# TCRT5000-Driver.net
KiCad netlist of a schematic drawn in EasyEDA
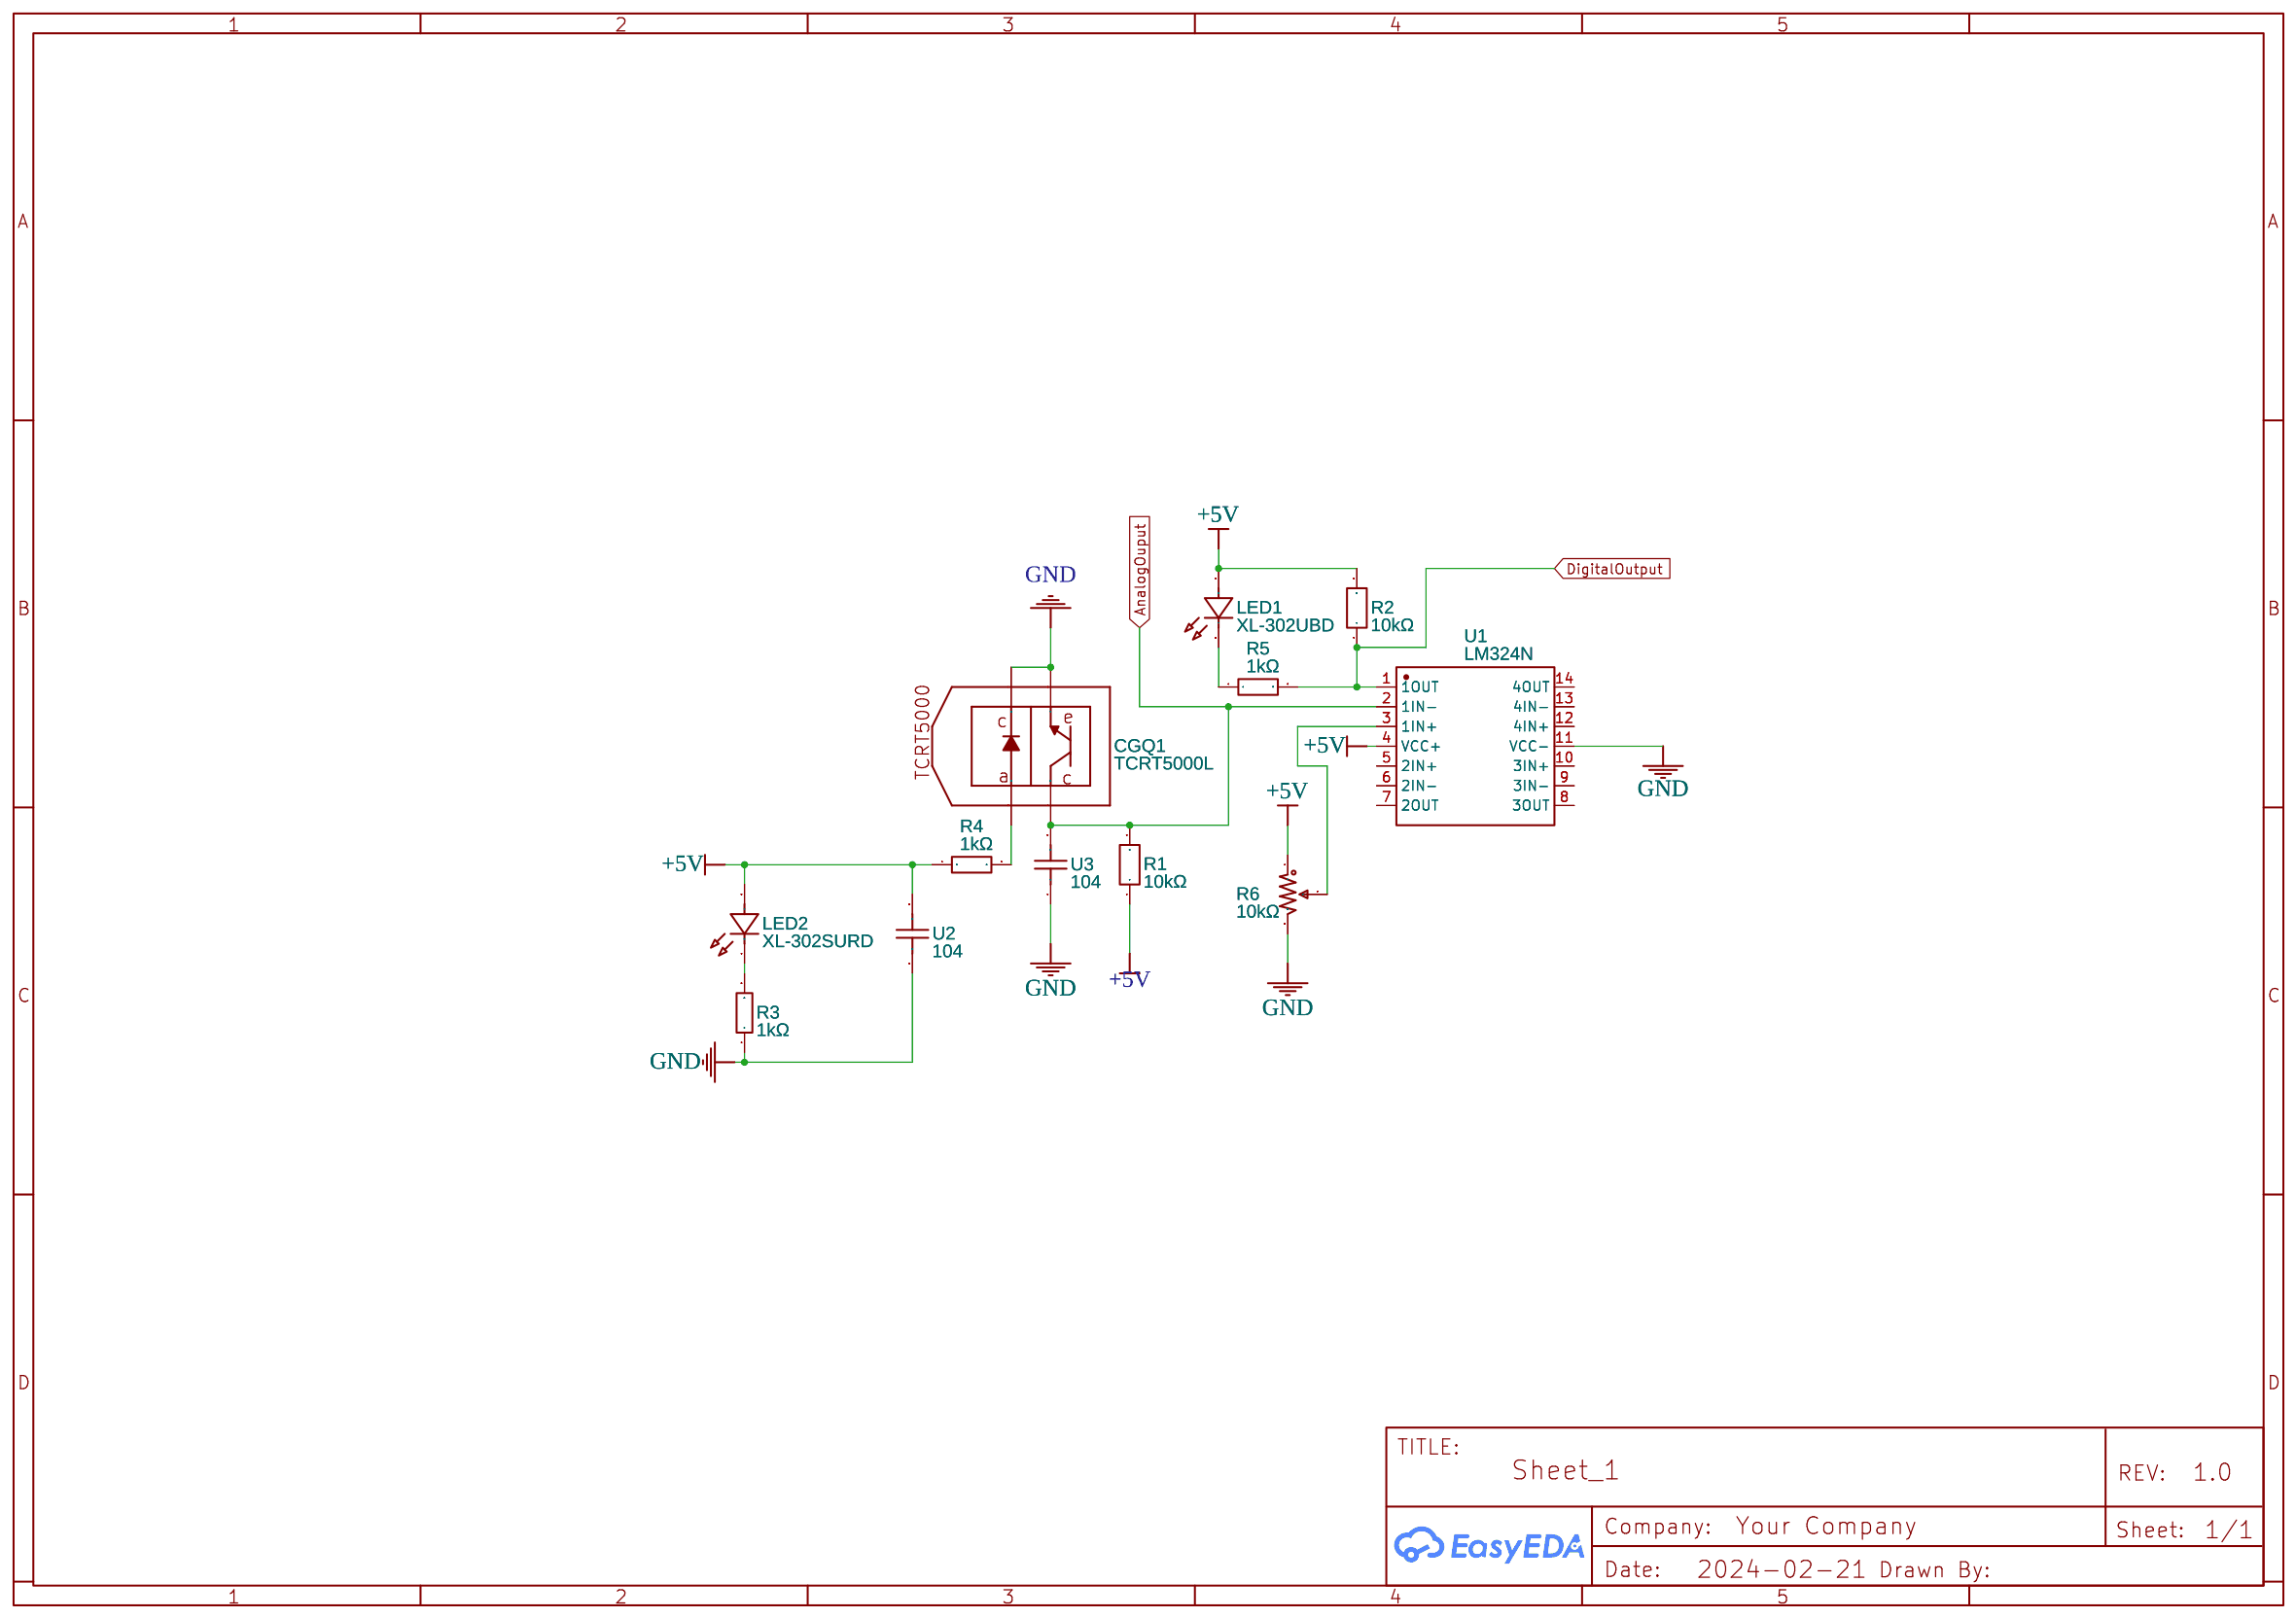
[diagram p0: schematic sheet]

(export (version "E")
  (design (tool "Eeschema 10.0.6"))
  (components
    (comp (ref "CGQ1")
      (value "TCRT5000L")
      (fields (field (name "Manufacturer") "VISHAY(威世)"))
      (libsource (lib "") (part "TCRT5000L"))
    )
    (comp (ref "LED1")
      (value "XL-302UBD")
      (fields (field (name "Manufacturer") "XINGLIGHT(成兴光)"))
      (libsource (lib "") (part "XL-302UBD"))
    )
    (comp (ref "LED2")
      (value "XL-302SURD")
      (fields (field (name "Manufacturer") "XINGLIGHT(成兴光)"))
      (libsource (lib "") (part "XL-302SURD"))
    )
    (comp (ref "R1")
      (value "10kΩ")
      (fields
        (field (name "Manufacturer Part") "RD1/4W10KJT/BA1")
        (field (name "Manufacturer") "Tyohm(幸亚电阻)")
      )
      (libsource (lib "") (part "RD 1/4W 10K J T/B A1"))
    )
    (comp (ref "R2")
      (value "10kΩ")
      (fields
        (field (name "Manufacturer Part") "RD1/4W10KJT/BA1")
        (field (name "Manufacturer") "Tyohm(幸亚电阻)")
      )
      (libsource (lib "") (part "RD 1/4W 10K J T/B A1"))
    )
    (comp (ref "R3")
      (value "1kΩ")
      (fields (field (name "Manufacturer Part") "CR1/4W-1K±5%-ST26") (field (name "Manufacturer") "VO(翔胜)"))
      (libsource (lib "") (part "CR1/4W-1K±5%-ST26_1"))
    )
    (comp (ref "R4")
      (value "1kΩ")
      (fields (field (name "Manufacturer Part") "CR1/4W-1K±5%-ST26") (field (name "Manufacturer") "VO(翔胜)"))
      (libsource (lib "") (part "CR1/4W-1K±5%-ST26"))
    )
    (comp (ref "R5")
      (value "1kΩ")
      (fields (field (name "Manufacturer Part") "CR1/4W-1K±5%-ST26") (field (name "Manufacturer") "VO(翔胜)"))
      (libsource (lib "") (part "CR1/4W-1K±5%-ST26"))
    )
    (comp (ref "R6")
      (value "10kΩ")
      (fields (field (name "Manufacturer Part") "RM065-103(10K)") (field (name "Manufacturer") "BOCHEN(博晨)"))
      (libsource (lib "") (part "RM065-103(10K)"))
    )
    (comp (ref "U1")
      (value "LM324N")
      (fields (field (name "Manufacturer") "TI(德州仪器)"))
      (libsource (lib "") (part "LM324N"))
    )
    (comp (ref "U2")
      (value "104")
      (fields
        (field (name "Manufacturer Part") "CC1H104MC1FD3F6C10SA")
        (field (name "Manufacturer") "Dersonic(德尔创)")
      )
      (libsource (lib "") (part "CC1H104MC1FD3F6C10SA"))
    )
    (comp (ref "U3")
      (value "104")
      (fields
        (field (name "Manufacturer Part") "CC1H104MC1FD3F6C10SA")
        (field (name "Manufacturer") "Dersonic(德尔创)")
      )
      (libsource (lib "") (part "CC1H104MC1FD3F6C10SA"))
    )
  )
  (nets
    (net (code "1") (name "+5V") (class "Default")
      (node (ref "LED1") (pin "1") (pinfunction "K_1") (pintype "unspecified"))
      (node (ref "LED2") (pin "2") (pinfunction "A_2") (pintype "unspecified"))
      (node (ref "R1") (pin "1") (pinfunction "1_1") (pintype "unspecified"))
      (node (ref "R2") (pin "2") (pinfunction "2_2") (pintype "unspecified"))
      (node (ref "R4") (pin "1") (pinfunction "1_1") (pintype "unspecified"))
      (node (ref "R6") (pin "1") (pinfunction "1_1") (pintype "unspecified"))
      (node (ref "U1") (pin "4") (pinfunction "VCC+_4") (pintype "unspecified"))
      (node (ref "U2") (pin "2") (pinfunction "2_2") (pintype "unspecified"))
    )
    (net (code "2") (name "AnalogOuput") (class "Default")
      (node (ref "CGQ1") (pin "1") (pinfunction "C_1") (pintype "unspecified"))
      (node (ref "R1") (pin "2") (pinfunction "2_2") (pintype "unspecified"))
      (node (ref "U1") (pin "2") (pinfunction "1IN-_2") (pintype "unspecified"))
      (node (ref "U3") (pin "2") (pinfunction "2_2") (pintype "unspecified"))
    )
    (net (code "3") (name "DigitalOutput") (class "Default")
      (node (ref "R2") (pin "1") (pinfunction "1_1") (pintype "unspecified"))
      (node (ref "R5") (pin "2") (pinfunction "2_2") (pintype "unspecified"))
      (node (ref "U1") (pin "1") (pinfunction "1OUT_1") (pintype "unspecified"))
    )
    (net (code "4") (name "GND") (class "Default")
      (node (ref "CGQ1") (pin "2") (pinfunction "E_2") (pintype "unspecified"))
      (node (ref "CGQ1") (pin "4") (pinfunction "C_4") (pintype "unspecified"))
      (node (ref "R3") (pin "1") (pinfunction "1_1") (pintype "unspecified"))
      (node (ref "R6") (pin "3") (pinfunction "3_3") (pintype "unspecified"))
      (node (ref "U1") (pin "11") (pinfunction "VCC-_11") (pintype "unspecified"))
      (node (ref "U2") (pin "1") (pinfunction "1_1") (pintype "unspecified"))
      (node (ref "U3") (pin "1") (pinfunction "1_1") (pintype "unspecified"))
    )
    (net (code "5") (name "Net-(CGQ1-A)") (class "Default")
      (node (ref "CGQ1") (pin "3") (pinfunction "A_3") (pintype "unspecified"))
      (node (ref "R4") (pin "2") (pinfunction "2_2") (pintype "unspecified"))
    )
    (net (code "6") (name "Net-(LED1-A)") (class "Default")
      (node (ref "LED1") (pin "2") (pinfunction "A_2") (pintype "unspecified"))
      (node (ref "R5") (pin "1") (pinfunction "1_1") (pintype "unspecified"))
    )
    (net (code "7") (name "Net-(LED2-K)") (class "Default")
      (node (ref "LED2") (pin "1") (pinfunction "K_1") (pintype "unspecified"))
      (node (ref "R3") (pin "2") (pinfunction "2_2") (pintype "unspecified"))
    )
    (net (code "8") (name "Net-(U1-1IN+)") (class "Default")
      (node (ref "R6") (pin "2") (pinfunction "2_2") (pintype "unspecified"))
      (node (ref "U1") (pin "3") (pinfunction "1IN+_3") (pintype "unspecified"))
    )
    (net (code "9") (name "unconnected-(U1-2IN+-Pad5)") (class "Default")
      (node (ref "U1") (pin "5") (pinfunction "2IN+_5") (pintype "unspecified"))
    )
    (net (code "10") (name "unconnected-(U1-2IN--Pad6)") (class "Default")
      (node (ref "U1") (pin "6") (pinfunction "2IN-_6") (pintype "unspecified"))
    )
    (net (code "11") (name "unconnected-(U1-2OUT-Pad7)") (class "Default")
      (node (ref "U1") (pin "7") (pinfunction "2OUT_7") (pintype "unspecified"))
    )
    (net (code "12") (name "unconnected-(U1-3IN+-Pad10)") (class "Default")
      (node (ref "U1") (pin "10") (pinfunction "3IN+_10") (pintype "unspecified"))
    )
    (net (code "13") (name "unconnected-(U1-3IN--Pad9)") (class "Default")
      (node (ref "U1") (pin "9") (pinfunction "3IN-_9") (pintype "unspecified"))
    )
    (net (code "14") (name "unconnected-(U1-3OUT-Pad8)") (class "Default")
      (node (ref "U1") (pin "8") (pinfunction "3OUT_8") (pintype "unspecified"))
    )
    (net (code "15") (name "unconnected-(U1-4IN+-Pad12)") (class "Default")
      (node (ref "U1") (pin "12") (pinfunction "4IN+_12") (pintype "unspecified"))
    )
    (net (code "16") (name "unconnected-(U1-4IN--Pad13)") (class "Default")
      (node (ref "U1") (pin "13") (pinfunction "4IN-_13") (pintype "unspecified"))
    )
    (net (code "17") (name "unconnected-(U1-4OUT-Pad14)") (class "Default")
      (node (ref "U1") (pin "14") (pinfunction "4OUT_14") (pintype "unspecified"))
    )
  )
)
